# pyIMU_GPS.net
KiCad netlist of a schematic drawn in EAGLE
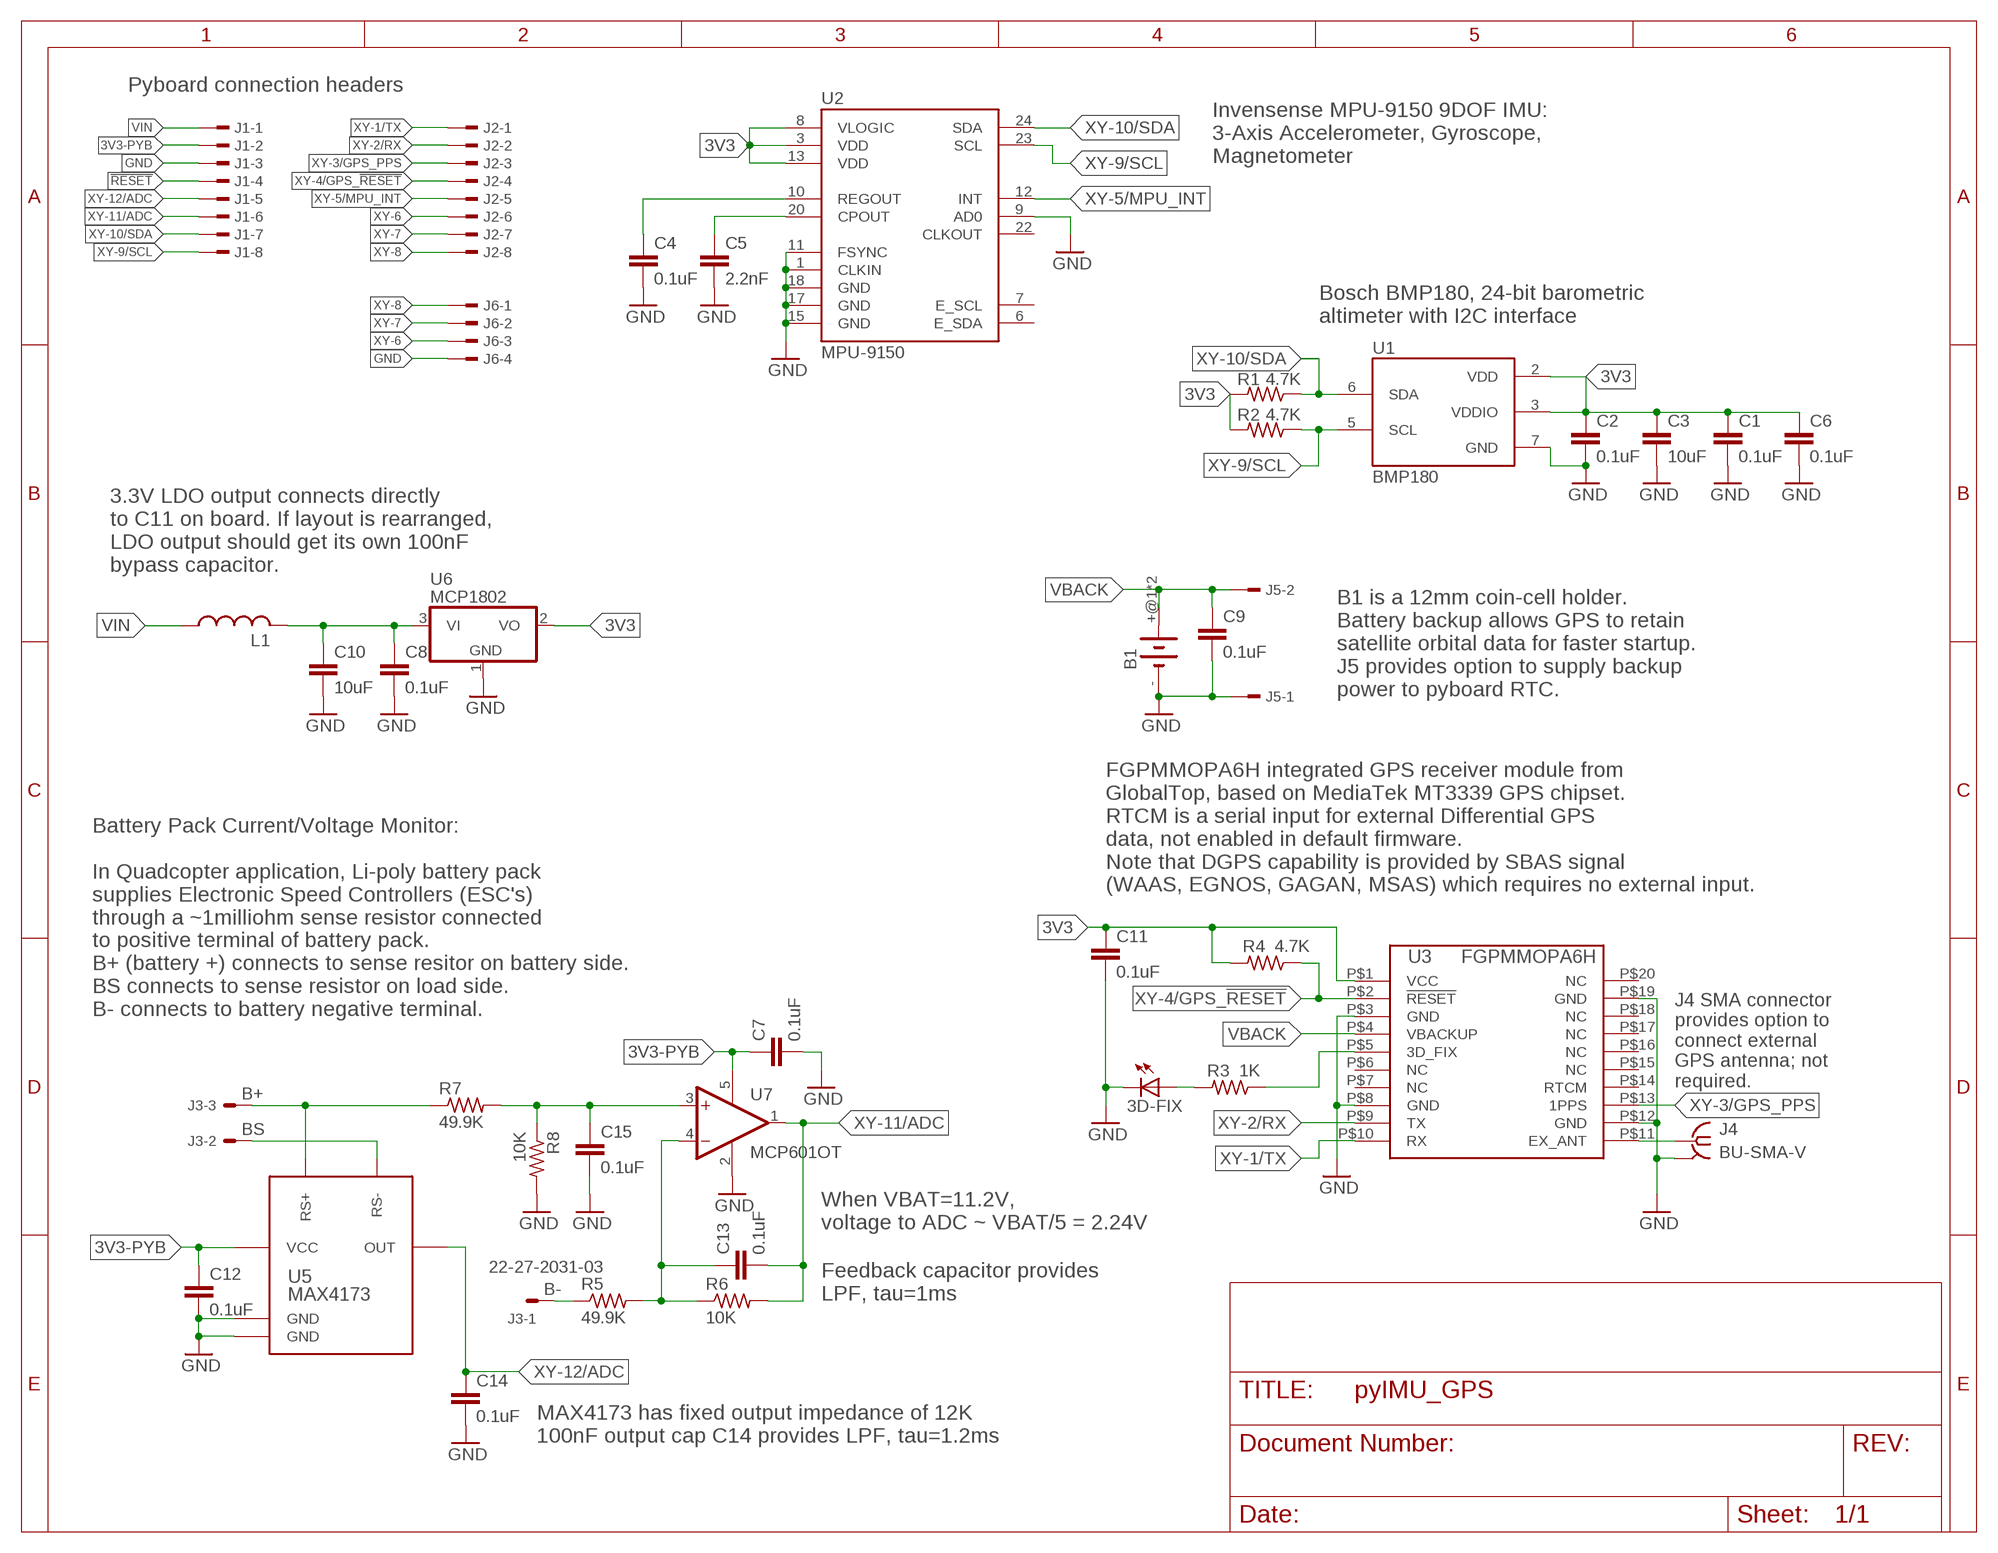
[diagram p0: schematic, sheet 1]

(export (version "E")
  (design (tool "Eeschema 10.0.6"))
  (components
    (comp (ref "3D-FIX")
      (value "LEDCHIPLED_0805")
      (footprint "eagle-import:CHIPLED_0805")
      (libsource (lib "eagle-import") (part "LEDCHIPLED_0805"))
    )
    (comp (ref "B1")
      (value "BATT_HOLDERK3000")
      (footprint "eagle-import:KEYSTONE-3000")
      (libsource (lib "eagle-import") (part "BATT_HOLDERK3000"))
    )
    (comp (ref "C1")
      (value "0.1uF")
      (footprint "eagle-import:C0603K")
      (libsource (lib "eagle-import") (part "C-EUC0603K"))
    )
    (comp (ref "C2")
      (value "0.1uF")
      (footprint "eagle-import:C0603K")
      (libsource (lib "eagle-import") (part "C-EUC0603K"))
    )
    (comp (ref "C3")
      (value "10uF")
      (footprint "eagle-import:C0805K")
      (libsource (lib "eagle-import") (part "C-EUC0805K"))
    )
    (comp (ref "C4")
      (value "0.1uF")
      (footprint "eagle-import:C0603K")
      (libsource (lib "eagle-import") (part "C-EUC0603K"))
    )
    (comp (ref "C5")
      (value "2.2nF")
      (footprint "eagle-import:C0603K")
      (libsource (lib "eagle-import") (part "C-EUC0603K"))
    )
    (comp (ref "C6")
      (value "0.1uF")
      (footprint "eagle-import:C0603K")
      (libsource (lib "eagle-import") (part "C-EUC0603K"))
    )
    (comp (ref "C7")
      (value "0.1uF")
      (footprint "eagle-import:C0603K")
      (libsource (lib "eagle-import") (part "C-EUC0603K"))
    )
    (comp (ref "C8")
      (value "0.1uF")
      (footprint "eagle-import:C0603K")
      (libsource (lib "eagle-import") (part "C-EUC0603K"))
    )
    (comp (ref "C9")
      (value "0.1uF")
      (footprint "eagle-import:C0603K")
      (libsource (lib "eagle-import") (part "C-EUC0603K"))
    )
    (comp (ref "C10")
      (value "10uF")
      (footprint "eagle-import:C0805K")
      (libsource (lib "eagle-import") (part "C-EUC0805K"))
    )
    (comp (ref "C11")
      (value "0.1uF")
      (footprint "eagle-import:C0603K")
      (libsource (lib "eagle-import") (part "C-EUC0603K"))
    )
    (comp (ref "C12")
      (value "0.1uF")
      (footprint "eagle-import:C0603K")
      (libsource (lib "eagle-import") (part "C-EUC0603K"))
    )
    (comp (ref "C13")
      (value "0.1uF")
      (footprint "eagle-import:C0603K")
      (libsource (lib "eagle-import") (part "C-EUC0603K"))
    )
    (comp (ref "C14")
      (value "0.1uF")
      (footprint "eagle-import:C0603K")
      (libsource (lib "eagle-import") (part "C-EUC0603K"))
    )
    (comp (ref "C15")
      (value "0.1uF")
      (footprint "eagle-import:C0603K")
      (libsource (lib "eagle-import") (part "C-EUC0603K"))
    )
    (comp (ref "J1")
      (value "TSW-108-02-S-S-MOD")
      (footprint "eagle-import:TSW-108-02-S-S-MOD")
      (libsource (lib "eagle-import") (part "TSW-108-02-S-S-MOD"))
    )
    (comp (ref "J2")
      (value "TSW-108-02-S-S-MOD")
      (footprint "eagle-import:TSW-108-02-S-S-MOD")
      (libsource (lib "eagle-import") (part "TSW-108-02-S-S-MOD"))
    )
    (comp (ref "J3")
      (value "22-27-2031-03")
      (footprint "eagle-import:6410-03")
      (libsource (lib "eagle-import") (part "22-?-0327-2031"))
    )
    (comp (ref "J4")
      (value "BU-SMA-V")
      (footprint "eagle-import:BU-SMA-V")
      (libsource (lib "eagle-import") (part "BU-SMA-V"))
    )
    (comp (ref "J5")
      (value "TSW-102-02-S-S")
      (footprint "eagle-import:TSW-102-02-S-S")
      (libsource (lib "eagle-import") (part "TSW-102-02-S-S"))
    )
    (comp (ref "J6")
      (value "TSW-104-02-S-S")
      (footprint "eagle-import:TSW-104-S-S-MOD")
      (libsource (lib "eagle-import") (part "TSW-104-02-S-S"))
    )
    (comp (ref "L1")
      (value "L-USL3216C")
      (footprint "eagle-import:L3216C")
      (libsource (lib "eagle-import") (part "L-USL3216C"))
    )
    (comp (ref "R1")
      (value "4.7K")
      (footprint "eagle-import:R0603")
      (libsource (lib "eagle-import") (part "R-US_R0603"))
    )
    (comp (ref "R2")
      (value "4.7K")
      (footprint "eagle-import:R0603")
      (libsource (lib "eagle-import") (part "R-US_R0603"))
    )
    (comp (ref "R3")
      (value "1K")
      (footprint "eagle-import:R0603")
      (libsource (lib "eagle-import") (part "R-US_R0603"))
    )
    (comp (ref "R4")
      (value "4.7K")
      (footprint "eagle-import:R0603")
      (libsource (lib "eagle-import") (part "R-US_R0603"))
    )
    (comp (ref "R5")
      (value "49.9K")
      (footprint "eagle-import:R0805")
      (libsource (lib "eagle-import") (part "R-US_R0805"))
    )
    (comp (ref "R6")
      (value "10K")
      (footprint "eagle-import:R0805")
      (libsource (lib "eagle-import") (part "R-US_R0805"))
    )
    (comp (ref "R7")
      (value "49.9K")
      (footprint "eagle-import:R0805")
      (libsource (lib "eagle-import") (part "R-US_R0805"))
    )
    (comp (ref "R8")
      (value "10K")
      (footprint "eagle-import:R0805")
      (libsource (lib "eagle-import") (part "R-US_R0805"))
    )
    (comp (ref "U1")
      (value "BMP180")
      (footprint "eagle-import:BMP180")
      (libsource (lib "eagle-import") (part "BMP180"))
    )
    (comp (ref "U2")
      (value "MPU-9150")
      (footprint "eagle-import:QFN-24-NP")
      (libsource (lib "eagle-import") (part "MPU-9150QFN-24-NP"))
    )
    (comp (ref "U3")
      (value "FGPMMOPA6H")
      (footprint "eagle-import:FGPMMOPA6H")
      (libsource (lib "eagle-import") (part "FGPMMOPA6H"))
    )
    (comp (ref "U5")
      (value "MAX4173")
      (footprint "eagle-import:SOT23-6L")
      (libsource (lib "eagle-import") (part "MAX4173"))
    )
    (comp (ref "U6")
      (value "MCP1802")
      (footprint "eagle-import:SOT23")
      (libsource (lib "eagle-import") (part "MCP1703CB"))
    )
    (comp (ref "U7")
      (value "MCP601OT")
      (footprint "eagle-import:SOT23-5")
      (libsource (lib "eagle-import") (part "MCP601OT"))
    )
  )
  (nets
    (net (code "1") (name "/B+") (class "Default")
      (node (ref "J3") (pin "3") (pinfunction "S_3") (pintype "passive"))
      (node (ref "R7") (pin "1") (pinfunction "1_1") (pintype "passive"))
      (node (ref "U5") (pin "4") (pinfunction "RS+_4") (pintype "input"))
    )
    (net (code "2") (name "/B-") (class "Default")
      (node (ref "J3") (pin "1") (pinfunction "S_1") (pintype "passive"))
      (node (ref "R5") (pin "1") (pinfunction "1_1") (pintype "passive"))
    )
    (net (code "3") (name "/BS") (class "Default")
      (node (ref "J3") (pin "2") (pinfunction "S_2") (pintype "passive"))
      (node (ref "U5") (pin "5") (pinfunction "RS-_5") (pintype "input"))
    )
    (net (code "4") (name "/XY-4{slash}GPS_~{RESET}") (class "Default")
      (node (ref "J2") (pin "4") (pinfunction "1_4") (pintype "passive"))
      (node (ref "R4") (pin "1") (pinfunction "1_1") (pintype "passive"))
      (node (ref "U3") (pin "P$2") (pinfunction "~{RESET}_P$2") (pintype "input"))
    )
    (net (code "5") (name "/~{RESET}") (class "Default")
      (node (ref "J1") (pin "4") (pinfunction "1_4") (pintype "passive"))
    )
    (net (code "6") (name "3V3") (class "Default")
      (node (ref "C1") (pin "1") (pinfunction "1_1") (pintype "passive"))
      (node (ref "C11") (pin "1") (pinfunction "1_1") (pintype "passive"))
      (node (ref "C2") (pin "1") (pinfunction "1_1") (pintype "passive"))
      (node (ref "C3") (pin "1") (pinfunction "1_1") (pintype "passive"))
      (node (ref "C6") (pin "1") (pinfunction "1_1") (pintype "passive"))
      (node (ref "R1") (pin "2") (pinfunction "2_2") (pintype "passive"))
      (node (ref "R2") (pin "2") (pinfunction "2_2") (pintype "passive"))
      (node (ref "R4") (pin "2") (pinfunction "2_2") (pintype "passive"))
      (node (ref "U1") (pin "2") (pinfunction "VDD_2") (pintype "power_in"))
      (node (ref "U1") (pin "3") (pinfunction "VDDIO_3") (pintype "power_in"))
      (node (ref "U2") (pin "13") (pinfunction "VDD_13") (pintype "bidirectional"))
      (node (ref "U2") (pin "3") (pinfunction "VDD_3") (pintype "bidirectional"))
      (node (ref "U2") (pin "8") (pinfunction "VLOGIC_8") (pintype "bidirectional"))
      (node (ref "U3") (pin "P$1") (pinfunction "VCC_P$1") (pintype "power_in"))
      (node (ref "U6") (pin "2") (pinfunction "VO_2") (pintype "passive"))
    )
    (net (code "7") (name "3V3-PYB") (class "Default")
      (node (ref "C12") (pin "1") (pinfunction "1_1") (pintype "passive"))
      (node (ref "C7") (pin "1") (pinfunction "1_1") (pintype "passive"))
      (node (ref "J1") (pin "2") (pinfunction "1_2") (pintype "passive"))
      (node (ref "U5") (pin "3") (pinfunction "VCC_3") (pintype "power_in"))
      (node (ref "U7") (pin "5") (pinfunction "V+_5") (pintype "power_in"))
    )
    (net (code "8") (name "GND") (class "Default")
      (node (ref "3D-FIX") (pin "C") (pinfunction "C_C") (pintype "passive"))
      (node (ref "B1") (pin "-") (pinfunction "-_-") (pintype "passive"))
      (node (ref "C1") (pin "2") (pinfunction "2_2") (pintype "passive"))
      (node (ref "C10") (pin "2") (pinfunction "2_2") (pintype "passive"))
      (node (ref "C11") (pin "2") (pinfunction "2_2") (pintype "passive"))
      (node (ref "C12") (pin "2") (pinfunction "2_2") (pintype "passive"))
      (node (ref "C14") (pin "2") (pinfunction "2_2") (pintype "passive"))
      (node (ref "C15") (pin "2") (pinfunction "2_2") (pintype "passive"))
      (node (ref "C2") (pin "2") (pinfunction "2_2") (pintype "passive"))
      (node (ref "C3") (pin "2") (pinfunction "2_2") (pintype "passive"))
      (node (ref "C4") (pin "2") (pinfunction "2_2") (pintype "passive"))
      (node (ref "C5") (pin "2") (pinfunction "2_2") (pintype "passive"))
      (node (ref "C6") (pin "2") (pinfunction "2_2") (pintype "passive"))
      (node (ref "C7") (pin "2") (pinfunction "2_2") (pintype "passive"))
      (node (ref "C8") (pin "2") (pinfunction "2_2") (pintype "passive"))
      (node (ref "C9") (pin "2") (pinfunction "2_2") (pintype "passive"))
      (node (ref "J1") (pin "3") (pinfunction "1_3") (pintype "passive"))
      (node (ref "J4") (pin "2") (pinfunction "2_2") (pintype "passive"))
      (node (ref "J4") (pin "3") (pinfunction "2_3") (pintype "passive"))
      (node (ref "J4") (pin "4") (pinfunction "2_4") (pintype "passive"))
      (node (ref "J4") (pin "5") (pinfunction "2_5") (pintype "passive"))
      (node (ref "J5") (pin "1") (pinfunction "1_1") (pintype "passive"))
      (node (ref "J6") (pin "4") (pinfunction "1_4") (pintype "passive"))
      (node (ref "R8") (pin "2") (pinfunction "2_2") (pintype "passive"))
      (node (ref "U1") (pin "7") (pinfunction "GND_7") (pintype "power_in"))
      (node (ref "U2") (pin "1") (pinfunction "CLKIN_1") (pintype "bidirectional"))
      (node (ref "U2") (pin "11") (pinfunction "FSYNC_11") (pintype "bidirectional"))
      (node (ref "U2") (pin "15") (pinfunction "GND_15") (pintype "bidirectional"))
      (node (ref "U2") (pin "17") (pinfunction "GND_17") (pintype "bidirectional"))
      (node (ref "U2") (pin "18") (pinfunction "GND_18") (pintype "bidirectional"))
      (node (ref "U2") (pin "9") (pinfunction "AD0_9") (pintype "bidirectional"))
      (node (ref "U3") (pin "P$12") (pinfunction "GND_P$12") (pintype "power_in"))
      (node (ref "U3") (pin "P$19") (pinfunction "GND_P$19") (pintype "power_in"))
      (node (ref "U3") (pin "P$3") (pinfunction "GND_P$3") (pintype "power_in"))
      (node (ref "U3") (pin "P$8") (pinfunction "GND_P$8") (pintype "power_in"))
      (node (ref "U5") (pin "1") (pinfunction "GND_1") (pintype "power_in"))
      (node (ref "U5") (pin "2") (pinfunction "GND_2") (pintype "power_in"))
      (node (ref "U6") (pin "1") (pinfunction "GND_1") (pintype "passive"))
      (node (ref "U7") (pin "2") (pinfunction "V-_2") (pintype "power_in"))
    )
    (net (code "9") (name "Net-(3D-FIX-PadA)") (class "Default")
      (node (ref "3D-FIX") (pin "A") (pinfunction "A_A") (pintype "passive"))
      (node (ref "R3") (pin "2") (pinfunction "2_2") (pintype "passive"))
    )
    (net (code "10") (name "Net-(U2-CPOUT)") (class "Default")
      (node (ref "C5") (pin "1") (pinfunction "1_1") (pintype "passive"))
      (node (ref "U2") (pin "20") (pinfunction "CPOUT_20") (pintype "bidirectional"))
    )
    (net (code "11") (name "Net-(U2-REGOUT)") (class "Default")
      (node (ref "C4") (pin "1") (pinfunction "1_1") (pintype "passive"))
      (node (ref "U2") (pin "10") (pinfunction "REGOUT_10") (pintype "bidirectional"))
    )
    (net (code "12") (name "Net-(U3-3D_FIX)") (class "Default")
      (node (ref "R3") (pin "1") (pinfunction "1_1") (pintype "passive"))
      (node (ref "U3") (pin "P$5") (pinfunction "3D_FIX_P$5") (pintype "output"))
    )
    (net (code "13") (name "Net-(U3-EX_ANT)") (class "Default")
      (node (ref "J4") (pin "1") (pinfunction "1_1") (pintype "passive"))
      (node (ref "U3") (pin "P$11") (pinfunction "EX_ANT_P$11") (pintype "input"))
    )
    (net (code "14") (name "Net-(U6-VI)") (class "Default")
      (node (ref "C10") (pin "1") (pinfunction "1_1") (pintype "passive"))
      (node (ref "C8") (pin "1") (pinfunction "1_1") (pintype "passive"))
      (node (ref "L1") (pin "2") (pinfunction "2_2") (pintype "passive"))
      (node (ref "U6") (pin "3") (pinfunction "VI_3") (pintype "input"))
    )
    (net (code "15") (name "Net-(U7-+IN)") (class "Default")
      (node (ref "C15") (pin "1") (pinfunction "1_1") (pintype "passive"))
      (node (ref "R7") (pin "2") (pinfunction "2_2") (pintype "passive"))
      (node (ref "R8") (pin "1") (pinfunction "1_1") (pintype "passive"))
      (node (ref "U7") (pin "3") (pinfunction "+IN_3") (pintype "input"))
    )
    (net (code "16") (name "Net-(U7--IN)") (class "Default")
      (node (ref "C13") (pin "1") (pinfunction "1_1") (pintype "passive"))
      (node (ref "R5") (pin "2") (pinfunction "2_2") (pintype "passive"))
      (node (ref "R6") (pin "1") (pinfunction "1_1") (pintype "passive"))
      (node (ref "U7") (pin "4") (pinfunction "-IN_4") (pintype "input"))
    )
    (net (code "17") (name "VBACK") (class "Default")
      (node (ref "B1") (pin "+@1") (pinfunction "+_+@1") (pintype "passive"))
      (node (ref "B1") (pin "+@2") (pinfunction "+_+@2") (pintype "passive"))
      (node (ref "C9") (pin "1") (pinfunction "1_1") (pintype "passive"))
      (node (ref "J5") (pin "2") (pinfunction "1_2") (pintype "passive"))
      (node (ref "U3") (pin "P$4") (pinfunction "VBACKUP_P$4") (pintype "power_in"))
    )
    (net (code "18") (name "VIN") (class "Default")
      (node (ref "J1") (pin "1") (pinfunction "1_1") (pintype "passive"))
      (node (ref "L1") (pin "1") (pinfunction "1_1") (pintype "passive"))
    )
    (net (code "19") (name "XY-1{slash}TX") (class "Default")
      (node (ref "J2") (pin "1") (pinfunction "1_1") (pintype "passive"))
      (node (ref "U3") (pin "P$10") (pinfunction "RX_P$10") (pintype "input"))
    )
    (net (code "20") (name "XY-2{slash}RX") (class "Default")
      (node (ref "J2") (pin "2") (pinfunction "1_2") (pintype "passive"))
      (node (ref "U3") (pin "P$9") (pinfunction "TX_P$9") (pintype "output"))
    )
    (net (code "21") (name "XY-3{slash}GPS_PPS") (class "Default")
      (node (ref "J2") (pin "3") (pinfunction "1_3") (pintype "passive"))
      (node (ref "U3") (pin "P$13") (pinfunction "1PPS_P$13") (pintype "output"))
    )
    (net (code "22") (name "XY-5{slash}MPU_INT") (class "Default")
      (node (ref "J2") (pin "5") (pinfunction "1_5") (pintype "passive"))
      (node (ref "U2") (pin "12") (pinfunction "INT_12") (pintype "bidirectional"))
    )
    (net (code "23") (name "XY-6") (class "Default")
      (node (ref "J2") (pin "6") (pinfunction "1_6") (pintype "passive"))
      (node (ref "J6") (pin "3") (pinfunction "1_3") (pintype "passive"))
    )
    (net (code "24") (name "XY-7") (class "Default")
      (node (ref "J2") (pin "7") (pinfunction "1_7") (pintype "passive"))
      (node (ref "J6") (pin "2") (pinfunction "1_2") (pintype "passive"))
    )
    (net (code "25") (name "XY-8") (class "Default")
      (node (ref "J2") (pin "8") (pinfunction "1_8") (pintype "passive"))
      (node (ref "J6") (pin "1") (pinfunction "1_1") (pintype "passive"))
    )
    (net (code "26") (name "XY-9{slash}SCL") (class "Default")
      (node (ref "J1") (pin "8") (pinfunction "1_8") (pintype "passive"))
      (node (ref "R2") (pin "1") (pinfunction "1_1") (pintype "passive"))
      (node (ref "U1") (pin "5") (pinfunction "SCL_5") (pintype "input"))
      (node (ref "U2") (pin "23") (pinfunction "SCL_23") (pintype "bidirectional"))
    )
    (net (code "27") (name "XY-10{slash}SDA") (class "Default")
      (node (ref "J1") (pin "7") (pinfunction "1_7") (pintype "passive"))
      (node (ref "R1") (pin "1") (pinfunction "1_1") (pintype "passive"))
      (node (ref "U1") (pin "6") (pinfunction "SDA_6") (pintype "bidirectional"))
      (node (ref "U2") (pin "24") (pinfunction "SDA_24") (pintype "bidirectional"))
    )
    (net (code "28") (name "XY-11{slash}ADC") (class "Default")
      (node (ref "C13") (pin "2") (pinfunction "2_2") (pintype "passive"))
      (node (ref "J1") (pin "6") (pinfunction "1_6") (pintype "passive"))
      (node (ref "R6") (pin "2") (pinfunction "2_2") (pintype "passive"))
      (node (ref "U7") (pin "1") (pinfunction "OUT_1") (pintype "output"))
    )
    (net (code "29") (name "XY-12{slash}ADC") (class "Default")
      (node (ref "C14") (pin "1") (pinfunction "1_1") (pintype "passive"))
      (node (ref "J1") (pin "5") (pinfunction "1_5") (pintype "passive"))
      (node (ref "U5") (pin "6") (pinfunction "OUT_6") (pintype "output"))
    )
    (net (code "30") (name "unconnected-(U2-CLKOUT-Pad22)") (class "Default")
      (node (ref "U2") (pin "22") (pinfunction "CLKOUT_22") (pintype "bidirectional"))
    )
    (net (code "31") (name "unconnected-(U2-E_SCL-Pad7)") (class "Default")
      (node (ref "U2") (pin "7") (pinfunction "E_SCL_7") (pintype "bidirectional"))
    )
    (net (code "32") (name "unconnected-(U2-E_SDA-Pad6)") (class "Default")
      (node (ref "U2") (pin "6") (pinfunction "E_SDA_6") (pintype "bidirectional"))
    )
    (net (code "33") (name "unconnected-(U3-NC-PadP$6)") (class "Default")
      (node (ref "U3") (pin "P$6") (pinfunction "NC_P$6") (pintype "no_connect"))
    )
    (net (code "34") (name "unconnected-(U3-NC-PadP$7)") (class "Default")
      (node (ref "U3") (pin "P$7") (pinfunction "NC_P$7") (pintype "no_connect"))
    )
    (net (code "35") (name "unconnected-(U3-NC-PadP$15)") (class "Default")
      (node (ref "U3") (pin "P$15") (pinfunction "NC_P$15") (pintype "no_connect"))
    )
    (net (code "36") (name "unconnected-(U3-NC-PadP$16)") (class "Default")
      (node (ref "U3") (pin "P$16") (pinfunction "NC_P$16") (pintype "no_connect"))
    )
    (net (code "37") (name "unconnected-(U3-NC-PadP$17)") (class "Default")
      (node (ref "U3") (pin "P$17") (pinfunction "NC_P$17") (pintype "no_connect"))
    )
    (net (code "38") (name "unconnected-(U3-NC-PadP$18)") (class "Default")
      (node (ref "U3") (pin "P$18") (pinfunction "NC_P$18") (pintype "no_connect"))
    )
    (net (code "39") (name "unconnected-(U3-NC-PadP$20)") (class "Default")
      (node (ref "U3") (pin "P$20") (pinfunction "NC_P$20") (pintype "no_connect"))
    )
    (net (code "40") (name "unconnected-(U3-RTCM-PadP$14)") (class "Default")
      (node (ref "U3") (pin "P$14") (pinfunction "RTCM_P$14") (pintype "input"))
    )
  )
)
